# sonoff_DIY_3_gang_SMD_version-V_1_1.net
KiCad netlist of a schematic drawn in EAGLE
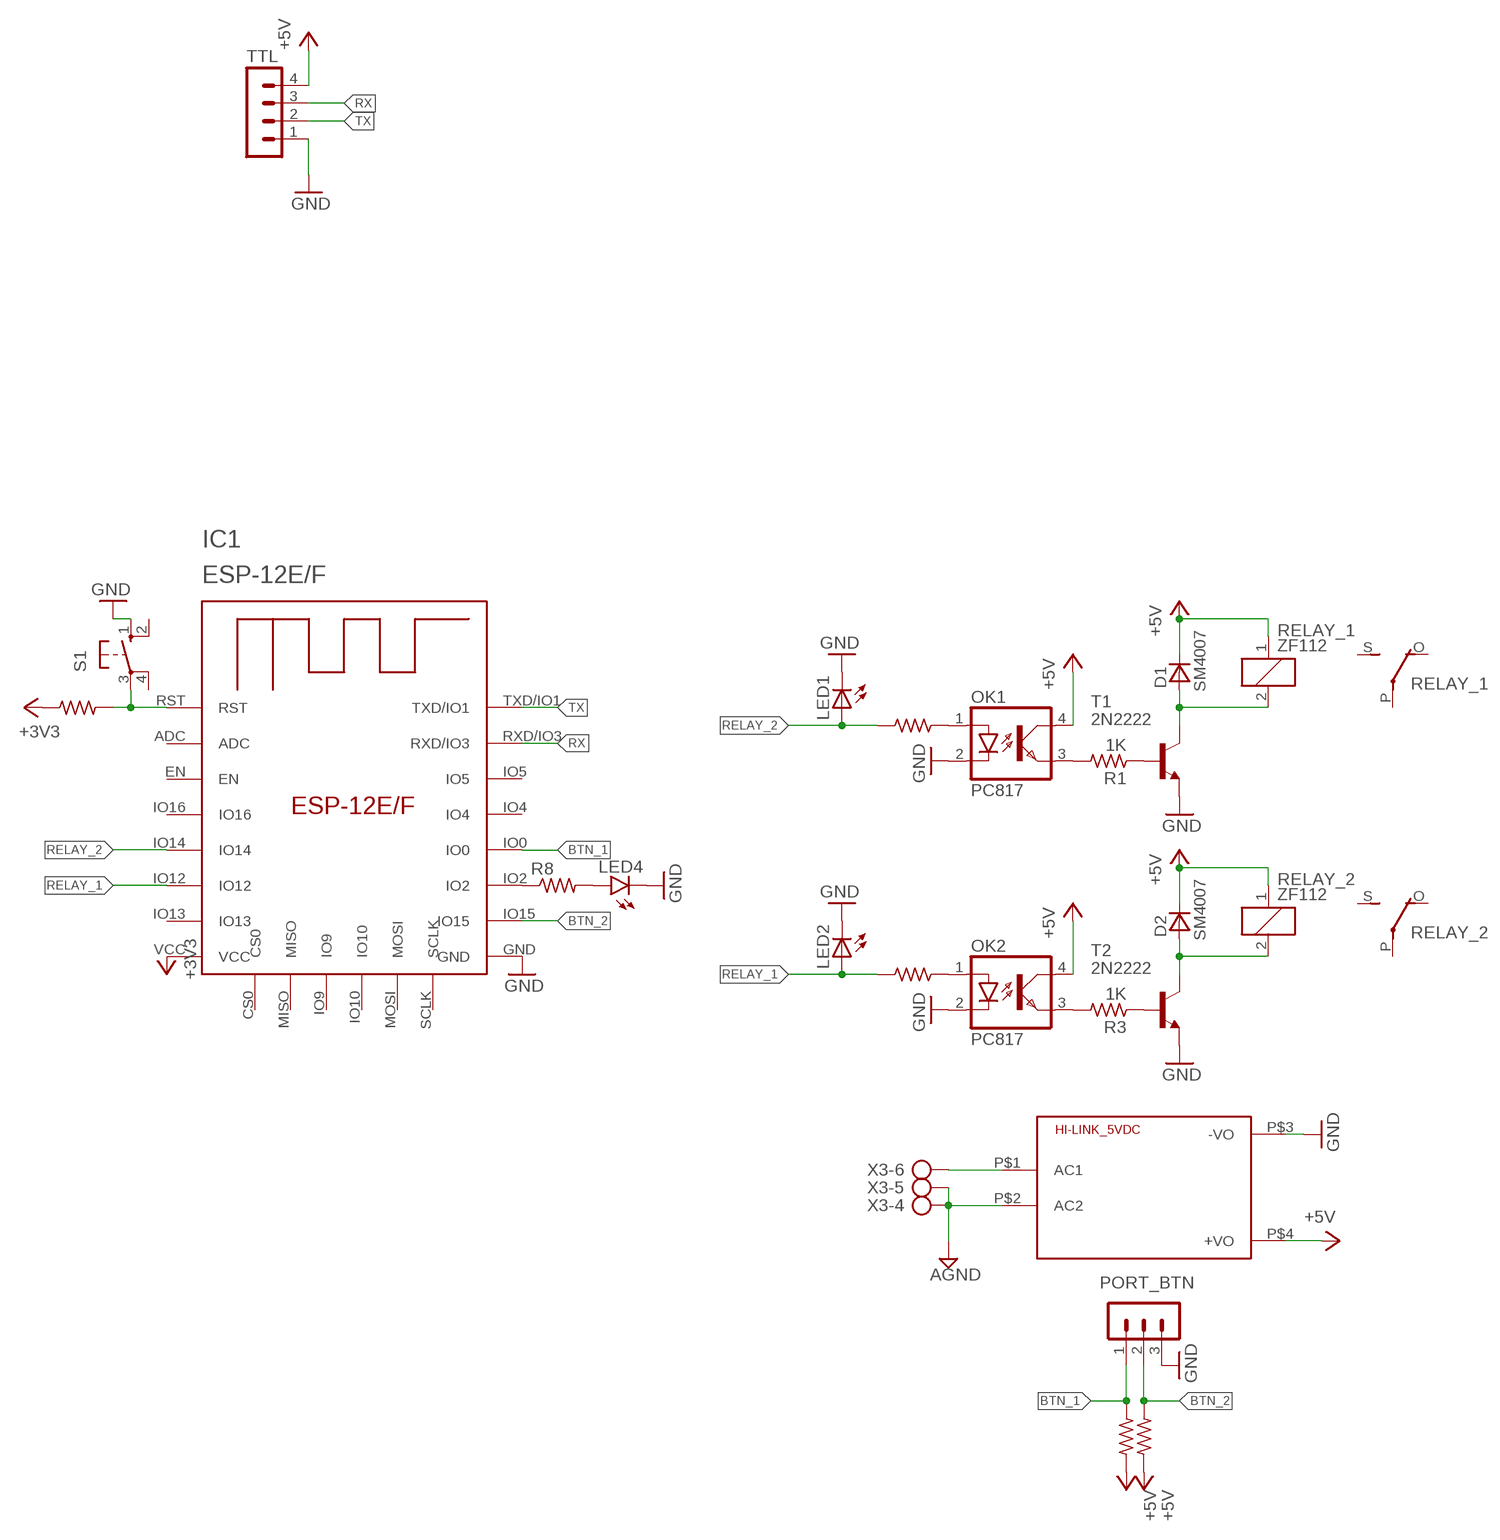
[diagram p0: schematic, sheet 1]

(export (version "E")
  (design (tool "Eeschema 10.0.6"))
  (components
    (comp (ref "D1")
      (value "SM4007")
      (footprint "eagle-import:MELF-MLL41")
      (libsource (lib "eagle-import") (part "SM4007"))
    )
    (comp (ref "D2")
      (value "SM4007")
      (footprint "eagle-import:MELF-MLL41")
      (libsource (lib "eagle-import") (part "SM4007"))
    )
    (comp (ref "HI-LINK_5VDC")
      (value "HLK-PM013W")
      (footprint "eagle-import:HLK-PM01")
      (libsource (lib "eagle-import") (part "HLK-PM013W"))
    )
    (comp (ref "IC1")
      (value "ESP-12E/F")
      (footprint "eagle-import:ESP-12E")
      (libsource (lib "eagle-import") (part "ESP-12E/F"))
    )
    (comp (ref "LED1")
      (value "LED3MM")
      (footprint "eagle-import:LED3MM")
      (libsource (lib "eagle-import") (part "LED3MM"))
    )
    (comp (ref "LED2")
      (value "LED3MM")
      (footprint "eagle-import:LED3MM")
      (libsource (lib "eagle-import") (part "LED3MM"))
    )
    (comp (ref "LED4")
      (value "LED3MM")
      (footprint "eagle-import:LED3MM")
      (libsource (lib "eagle-import") (part "led_259_LED3MM"))
    )
    (comp (ref "OK1")
      (value "PC817")
      (footprint "eagle-import:DIL04")
      (fields (field (name "MPN") "PC817X4J000F"))
      (libsource (lib "eagle-import") (part "PC817"))
    )
    (comp (ref "OK2")
      (value "PC817")
      (footprint "eagle-import:DIL04")
      (fields (field (name "MPN") "PC817X4J000F"))
      (libsource (lib "eagle-import") (part "PC817"))
    )
    (comp (ref "PORT_BTN")
      (value "MA03-1")
      (footprint "eagle-import:MA03-1")
      (libsource (lib "eagle-import") (part "MA03-1"))
    )
    (comp (ref "R1")
      (value "1K")
      (footprint "eagle-import:R0805")
      (libsource (lib "eagle-import") (part "R_0805"))
    )
    (comp (ref "R2")
      (value "1K")
      (footprint "eagle-import:R0805")
      (libsource (lib "eagle-import") (part "R_0805"))
    )
    (comp (ref "R3")
      (value "1K")
      (footprint "eagle-import:R0805")
      (libsource (lib "eagle-import") (part "R_0805"))
    )
    (comp (ref "R4")
      (value "1K")
      (footprint "eagle-import:R0805")
      (libsource (lib "eagle-import") (part "R_0805"))
    )
    (comp (ref "R5")
      (value "1K")
      (footprint "eagle-import:R0805")
      (libsource (lib "eagle-import") (part "R_0805"))
    )
    (comp (ref "R6")
      (value "1K")
      (footprint "eagle-import:R0805")
      (libsource (lib "eagle-import") (part "R_0805"))
    )
    (comp (ref "R7")
      (value "1K")
      (footprint "eagle-import:R0805")
      (libsource (lib "eagle-import") (part "R_0805"))
    )
    (comp (ref "R8")
      (value "R-US_0207/10")
      (footprint "eagle-import:0207_10")
      (libsource (lib "eagle-import") (part "R-US_0207/10"))
    )
    (comp (ref "RELAY_1")
      (value "ZF112")
      (footprint "eagle-import:ZF112")
      (libsource (lib "eagle-import") (part "ZF112"))
    )
    (comp (ref "RELAY_2")
      (value "ZF112")
      (footprint "eagle-import:ZF112")
      (libsource (lib "eagle-import") (part "ZF112"))
    )
    (comp (ref "S1")
      (value "10-XX")
      (footprint "eagle-import:B3F-10XX")
      (fields (field (name "MPN") "B3F-1000"))
      (libsource (lib "eagle-import") (part "10-XX"))
    )
    (comp (ref "T1")
      (value "2N2222")
      (footprint "eagle-import:TO18")
      (libsource (lib "eagle-import") (part "2N2222"))
    )
    (comp (ref "T2")
      (value "2N2222")
      (footprint "eagle-import:TO18")
      (libsource (lib "eagle-import") (part "2N2222"))
    )
    (comp (ref "TTL")
      (value "MA04-1")
      (footprint "eagle-import:MA04-1")
      (libsource (lib "eagle-import") (part "MA04-1"))
    )
    (comp (ref "X3")
      (value "SMKDSP_1,5/6")
      (footprint "eagle-import:SMKDSP_1,5_6")
      (fields (field (name "MF") "FARNELL") (field (name "MPN") "1733619"))
      (libsource (lib "eagle-import") (part "SMKDSP_1,5/6"))
    )
  )
  (nets
    (net (code "1") (name "+3V3") (class "Default")
      (node (ref "IC1") (pin "VCC") (pinfunction "VCC_VCC") (pintype "power_in"))
      (node (ref "R7") (pin "2") (pinfunction "2_2") (pintype "passive"))
    )
    (net (code "2") (name "+5V") (class "Default")
      (node (ref "D1") (pin "C") (pinfunction "C_C") (pintype "passive"))
      (node (ref "D2") (pin "C") (pinfunction "C_C") (pintype "passive"))
      (node (ref "HI-LINK_5VDC") (pin "P$4") (pinfunction "+VO_P$4") (pintype "bidirectional"))
      (node (ref "OK1") (pin "4") (pinfunction "COL_4") (pintype "passive"))
      (node (ref "OK2") (pin "4") (pinfunction "COL_4") (pintype "passive"))
      (node (ref "R5") (pin "2") (pinfunction "2_2") (pintype "passive"))
      (node (ref "R6") (pin "2") (pinfunction "2_2") (pintype "passive"))
      (node (ref "RELAY_1") (pin "1") (pinfunction "1_1") (pintype "passive"))
      (node (ref "RELAY_2") (pin "1") (pinfunction "1_1") (pintype "passive"))
      (node (ref "TTL") (pin "4") (pinfunction "4_4") (pintype "passive"))
    )
    (net (code "3") (name "AGND") (class "Default")
      (node (ref "HI-LINK_5VDC") (pin "P$2") (pinfunction "AC2_P$2") (pintype "bidirectional"))
      (node (ref "X3") (pin "4") (pinfunction "KL_4") (pintype "passive"))
      (node (ref "X3") (pin "5") (pinfunction "KL_5") (pintype "passive"))
    )
    (net (code "4") (name "BTN_1") (class "Default")
      (node (ref "IC1") (pin "IO0") (pinfunction "IO0_IO0") (pintype "bidirectional"))
      (node (ref "PORT_BTN") (pin "1") (pinfunction "1_1") (pintype "passive"))
      (node (ref "R5") (pin "1") (pinfunction "1_1") (pintype "passive"))
    )
    (net (code "5") (name "BTN_2") (class "Default")
      (node (ref "IC1") (pin "IO15") (pinfunction "IO15_IO15") (pintype "bidirectional"))
      (node (ref "PORT_BTN") (pin "2") (pinfunction "2_2") (pintype "passive"))
      (node (ref "R6") (pin "1") (pinfunction "1_1") (pintype "passive"))
    )
    (net (code "6") (name "GND") (class "Default")
      (node (ref "HI-LINK_5VDC") (pin "P$3") (pinfunction "-VO_P$3") (pintype "bidirectional"))
      (node (ref "IC1") (pin "GND") (pinfunction "GND_GND") (pintype "power_in"))
      (node (ref "LED1") (pin "K") (pinfunction "C_K") (pintype "passive"))
      (node (ref "LED2") (pin "K") (pinfunction "C_K") (pintype "passive"))
      (node (ref "LED4") (pin "K") (pinfunction "C_K") (pintype "passive"))
      (node (ref "OK1") (pin "2") (pinfunction "C_2") (pintype "passive"))
      (node (ref "OK2") (pin "2") (pinfunction "C_2") (pintype "passive"))
      (node (ref "PORT_BTN") (pin "3") (pinfunction "3_3") (pintype "passive"))
      (node (ref "S1") (pin "1") (pinfunction "S_1") (pintype "passive"))
      (node (ref "T1") (pin "1") (pinfunction "E_1") (pintype "passive"))
      (node (ref "T2") (pin "1") (pinfunction "E_1") (pintype "passive"))
      (node (ref "TTL") (pin "1") (pinfunction "1_1") (pintype "passive"))
    )
    (net (code "7") (name "Net-(HI-LINK_5VDC-AC1)") (class "Default")
      (node (ref "HI-LINK_5VDC") (pin "P$1") (pinfunction "AC1_P$1") (pintype "bidirectional"))
      (node (ref "X3") (pin "6") (pinfunction "KL_6") (pintype "passive"))
    )
    (net (code "8") (name "Net-(IC1-PadIO2)") (class "Default")
      (node (ref "IC1") (pin "IO2") (pinfunction "IO2_IO2") (pintype "bidirectional"))
      (node (ref "R8") (pin "1") (pinfunction "1_1") (pintype "passive"))
    )
    (net (code "9") (name "Net-(LED4-PadA)") (class "Default")
      (node (ref "LED4") (pin "A") (pinfunction "A_A") (pintype "passive"))
      (node (ref "R8") (pin "2") (pinfunction "2_2") (pintype "passive"))
    )
    (net (code "10") (name "Net-(OK1-A)") (class "Default")
      (node (ref "OK1") (pin "1") (pinfunction "A_1") (pintype "passive"))
      (node (ref "R2") (pin "1") (pinfunction "1_1") (pintype "passive"))
    )
    (net (code "11") (name "Net-(OK1-EMIT)") (class "Default")
      (node (ref "OK1") (pin "3") (pinfunction "EMIT_3") (pintype "passive"))
      (node (ref "R1") (pin "2") (pinfunction "2_2") (pintype "passive"))
    )
    (net (code "12") (name "Net-(OK2-A)") (class "Default")
      (node (ref "OK2") (pin "1") (pinfunction "A_1") (pintype "passive"))
      (node (ref "R4") (pin "1") (pinfunction "1_1") (pintype "passive"))
    )
    (net (code "13") (name "Net-(OK2-EMIT)") (class "Default")
      (node (ref "OK2") (pin "3") (pinfunction "EMIT_3") (pintype "passive"))
      (node (ref "R3") (pin "2") (pinfunction "2_2") (pintype "passive"))
    )
    (net (code "14") (name "Net-(S1-P)") (class "Default")
      (node (ref "IC1") (pin "RST") (pinfunction "RST_RST") (pintype "input"))
      (node (ref "R7") (pin "1") (pinfunction "1_1") (pintype "passive"))
      (node (ref "S1") (pin "3") (pinfunction "P_3") (pintype "passive"))
    )
    (net (code "15") (name "Net-(T1-B)") (class "Default")
      (node (ref "R1") (pin "1") (pinfunction "1_1") (pintype "passive"))
      (node (ref "T1") (pin "2") (pinfunction "B_2") (pintype "passive"))
    )
    (net (code "16") (name "Net-(T1-C)") (class "Default")
      (node (ref "D1") (pin "A") (pinfunction "A_A") (pintype "passive"))
      (node (ref "RELAY_1") (pin "2") (pinfunction "2_2") (pintype "passive"))
      (node (ref "T1") (pin "3") (pinfunction "C_3") (pintype "passive"))
    )
    (net (code "17") (name "Net-(T2-B)") (class "Default")
      (node (ref "R3") (pin "1") (pinfunction "1_1") (pintype "passive"))
      (node (ref "T2") (pin "2") (pinfunction "B_2") (pintype "passive"))
    )
    (net (code "18") (name "Net-(T2-C)") (class "Default")
      (node (ref "D2") (pin "A") (pinfunction "A_A") (pintype "passive"))
      (node (ref "RELAY_2") (pin "2") (pinfunction "2_2") (pintype "passive"))
      (node (ref "T2") (pin "3") (pinfunction "C_3") (pintype "passive"))
    )
    (net (code "19") (name "RELAY_1") (class "Default")
      (node (ref "IC1") (pin "IO12") (pinfunction "IO12_IO12") (pintype "bidirectional"))
      (node (ref "LED2") (pin "A") (pinfunction "A_A") (pintype "passive"))
      (node (ref "R4") (pin "2") (pinfunction "2_2") (pintype "passive"))
    )
    (net (code "20") (name "RELAY_2") (class "Default")
      (node (ref "IC1") (pin "IO14") (pinfunction "IO14_IO14") (pintype "bidirectional"))
      (node (ref "LED1") (pin "A") (pinfunction "A_A") (pintype "passive"))
      (node (ref "R2") (pin "2") (pinfunction "2_2") (pintype "passive"))
    )
    (net (code "21") (name "RX") (class "Default")
      (node (ref "IC1") (pin "RXD/IO3") (pinfunction "RXD/IO3_RXD/IO3") (pintype "bidirectional"))
      (node (ref "TTL") (pin "3") (pinfunction "3_3") (pintype "passive"))
    )
    (net (code "22") (name "TX") (class "Default")
      (node (ref "IC1") (pin "TXD/IO1") (pinfunction "TXD/IO1_TXD/IO1") (pintype "bidirectional"))
      (node (ref "TTL") (pin "2") (pinfunction "2_2") (pintype "passive"))
    )
    (net (code "23") (name "unconnected-(IC1-PadADC)") (class "Default")
      (node (ref "IC1") (pin "ADC") (pinfunction "ADC_ADC") (pintype "bidirectional"))
    )
    (net (code "24") (name "unconnected-(IC1-PadCS0)") (class "Default")
      (node (ref "IC1") (pin "CS0") (pinfunction "CS0_CS0") (pintype "bidirectional"))
    )
    (net (code "25") (name "unconnected-(IC1-PadEN)") (class "Default")
      (node (ref "IC1") (pin "EN") (pinfunction "EN_EN") (pintype "bidirectional"))
    )
    (net (code "26") (name "unconnected-(IC1-PadIO4)") (class "Default")
      (node (ref "IC1") (pin "IO4") (pinfunction "IO4_IO4") (pintype "bidirectional"))
    )
    (net (code "27") (name "unconnected-(IC1-PadIO5)") (class "Default")
      (node (ref "IC1") (pin "IO5") (pinfunction "IO5_IO5") (pintype "bidirectional"))
    )
    (net (code "28") (name "unconnected-(IC1-PadIO9)") (class "Default")
      (node (ref "IC1") (pin "IO9") (pinfunction "IO9_IO9") (pintype "bidirectional"))
    )
    (net (code "29") (name "unconnected-(IC1-PadIO10)") (class "Default")
      (node (ref "IC1") (pin "IO10") (pinfunction "IO10_IO10") (pintype "bidirectional"))
    )
    (net (code "30") (name "unconnected-(IC1-PadIO13)") (class "Default")
      (node (ref "IC1") (pin "IO13") (pinfunction "IO13_IO13") (pintype "bidirectional"))
    )
    (net (code "31") (name "unconnected-(IC1-PadIO16)") (class "Default")
      (node (ref "IC1") (pin "IO16") (pinfunction "IO16_IO16") (pintype "bidirectional"))
    )
    (net (code "32") (name "unconnected-(IC1-PadMISO)") (class "Default")
      (node (ref "IC1") (pin "MISO") (pinfunction "MISO_MISO") (pintype "bidirectional"))
    )
    (net (code "33") (name "unconnected-(IC1-PadMOSI)") (class "Default")
      (node (ref "IC1") (pin "MOSI") (pinfunction "MOSI_MOSI") (pintype "bidirectional"))
    )
    (net (code "34") (name "unconnected-(IC1-PadSCLK)") (class "Default")
      (node (ref "IC1") (pin "SCLK") (pinfunction "SCLK_SCLK") (pintype "bidirectional"))
    )
    (net (code "35") (name "unconnected-(RELAY_1-PadO)") (class "Default")
      (node (ref "RELAY_1") (pin "O") (pinfunction "O_O") (pintype "passive"))
    )
    (net (code "36") (name "unconnected-(RELAY_1-PadP)") (class "Default")
      (node (ref "RELAY_1") (pin "P") (pinfunction "P_P") (pintype "passive"))
    )
    (net (code "37") (name "unconnected-(RELAY_1-PadS)") (class "Default")
      (node (ref "RELAY_1") (pin "S") (pinfunction "S_S") (pintype "passive"))
    )
    (net (code "38") (name "unconnected-(RELAY_2-PadO)") (class "Default")
      (node (ref "RELAY_2") (pin "O") (pinfunction "O_O") (pintype "passive"))
    )
    (net (code "39") (name "unconnected-(RELAY_2-PadP)") (class "Default")
      (node (ref "RELAY_2") (pin "P") (pinfunction "P_P") (pintype "passive"))
    )
    (net (code "40") (name "unconnected-(RELAY_2-PadS)") (class "Default")
      (node (ref "RELAY_2") (pin "S") (pinfunction "S_S") (pintype "passive"))
    )
    (net (code "41") (name "unconnected-(S1-P1-Pad4)") (class "Default")
      (node (ref "S1") (pin "4") (pinfunction "P1_4") (pintype "passive"))
    )
    (net (code "42") (name "unconnected-(S1-S1-Pad2)") (class "Default")
      (node (ref "S1") (pin "2") (pinfunction "S1_2") (pintype "passive"))
    )
  )
)
